# ds1307.net
KiCad netlist of a schematic drawn in EAGLE
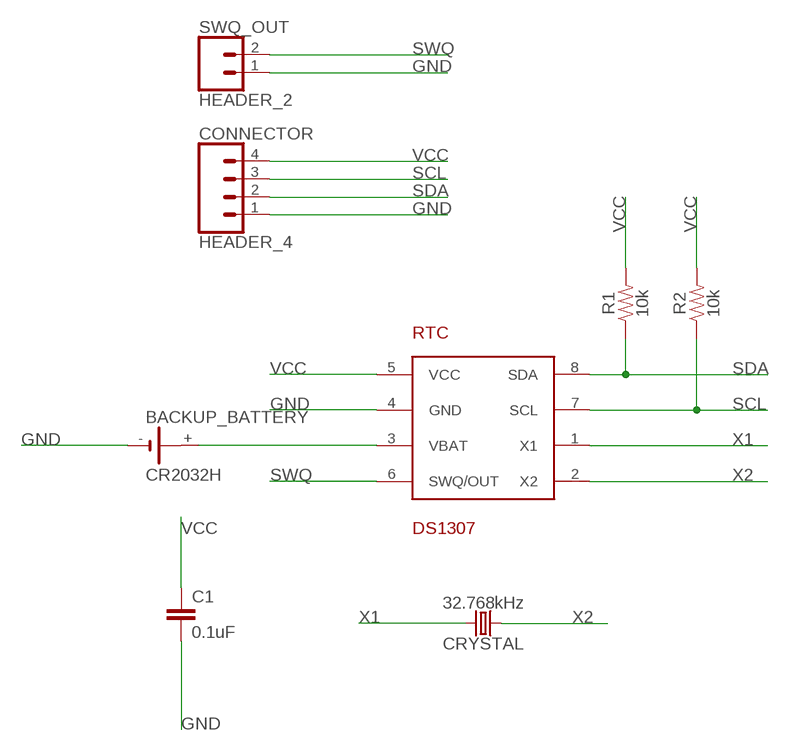
[diagram p0: schematic, sheet 1]

(export (version "E")
  (design (tool "Eeschema 10.0.6"))
  (components
    (comp (ref "BACKUP_BATTERY")
      (value "CR2032H")
      (footprint "eagle-import:CR2032H")
      (libsource (lib "eagle-import") (part "CR2032H"))
    )
    (comp (ref "C1")
      (value "0.1uF")
      (footprint "eagle-import:CAP-PTH-SMALL-KIT")
      (libsource (lib "eagle-import") (part "0.1UF-KIT-EZ-50V-20%"))
    )
    (comp (ref "CONNECTOR")
      (value "HEADER_4")
      (footprint "eagle-import:MOLEX-1X4")
      (libsource (lib "eagle-import") (part "CONN_04POLAR"))
    )
    (comp (ref "CRYSTAL")
      (value "32.768kHz")
      (footprint "eagle-import:CRYSTAL-PTH-2X6-CYL")
      (libsource (lib "eagle-import") (part "CRYSTAL-32.768KHZPTH-2X6"))
    )
    (comp (ref "R1")
      (value "10k")
      (footprint "eagle-import:AXIAL-0.3")
      (libsource (lib "eagle-import") (part "10KOHM-HORIZ-1/4W-1%"))
    )
    (comp (ref "R2")
      (value "10k")
      (footprint "eagle-import:AXIAL-0.3")
      (libsource (lib "eagle-import") (part "10KOHM-HORIZ-1/4W-1%"))
    )
    (comp (ref "RTC")
      (value "DS1307")
      (footprint "eagle-import:MAXIM_DIP8")
      (libsource (lib "eagle-import") (part "DS1307"))
    )
    (comp (ref "SWQ_OUT")
      (value "HEADER_2")
      (footprint "eagle-import:1X02")
      (libsource (lib "eagle-import") (part "CONN_02"))
    )
  )
  (nets
    (net (code "1") (name "/GND") (class "Default")
      (node (ref "BACKUP_BATTERY") (pin "-") (pinfunction "-_-") (pintype "passive"))
      (node (ref "C1") (pin "2") (pinfunction "2_2") (pintype "passive"))
      (node (ref "CONNECTOR") (pin "1") (pinfunction "1_1") (pintype "passive"))
      (node (ref "RTC") (pin "4") (pinfunction "GND_4") (pintype "power_in"))
      (node (ref "SWQ_OUT") (pin "1") (pinfunction "1_1") (pintype "passive"))
    )
    (net (code "2") (name "/SCL") (class "Default")
      (node (ref "CONNECTOR") (pin "3") (pinfunction "3_3") (pintype "passive"))
      (node (ref "R2") (pin "P$1") (pinfunction "1_P$1") (pintype "passive"))
      (node (ref "RTC") (pin "7") (pinfunction "SCL_7") (pintype "bidirectional"))
    )
    (net (code "3") (name "/SDA") (class "Default")
      (node (ref "CONNECTOR") (pin "2") (pinfunction "2_2") (pintype "passive"))
      (node (ref "R1") (pin "P$1") (pinfunction "1_P$1") (pintype "passive"))
      (node (ref "RTC") (pin "8") (pinfunction "SDA_8") (pintype "bidirectional"))
    )
    (net (code "4") (name "/SWQ") (class "Default")
      (node (ref "RTC") (pin "6") (pinfunction "SWQ/OUT_6") (pintype "output"))
      (node (ref "SWQ_OUT") (pin "2") (pinfunction "2_2") (pintype "passive"))
    )
    (net (code "5") (name "/VCC") (class "Default")
      (node (ref "C1") (pin "1") (pinfunction "1_1") (pintype "passive"))
      (node (ref "CONNECTOR") (pin "4") (pinfunction "4_4") (pintype "passive"))
      (node (ref "R1") (pin "P$2") (pinfunction "2_P$2") (pintype "passive"))
      (node (ref "R2") (pin "P$2") (pinfunction "2_P$2") (pintype "passive"))
      (node (ref "RTC") (pin "5") (pinfunction "VCC_5") (pintype "power_in"))
    )
    (net (code "6") (name "/X1") (class "Default")
      (node (ref "CRYSTAL") (pin "2") (pinfunction "2_2") (pintype "passive"))
      (node (ref "RTC") (pin "1") (pinfunction "X1_1") (pintype "bidirectional"))
    )
    (net (code "7") (name "/X2") (class "Default")
      (node (ref "CRYSTAL") (pin "1") (pinfunction "1_1") (pintype "passive"))
      (node (ref "RTC") (pin "2") (pinfunction "X2_2") (pintype "bidirectional"))
    )
    (net (code "8") (name "Net-(RTC-VBAT)") (class "Default")
      (node (ref "BACKUP_BATTERY") (pin "+") (pinfunction "+_+") (pintype "passive"))
      (node (ref "RTC") (pin "3") (pinfunction "VBAT_3") (pintype "power_in"))
    )
    (net (code "9") (name "unconnected-(BACKUP_BATTERY-+-Pad+@1)") (class "Default")
      (node (ref "BACKUP_BATTERY") (pin "+@1") (pinfunction "+_+@1") (pintype "passive"))
    )
  )
)
